# CH32F203VCT6-R0.net
KiCad netlist of a schematic drawn in Altium Designer
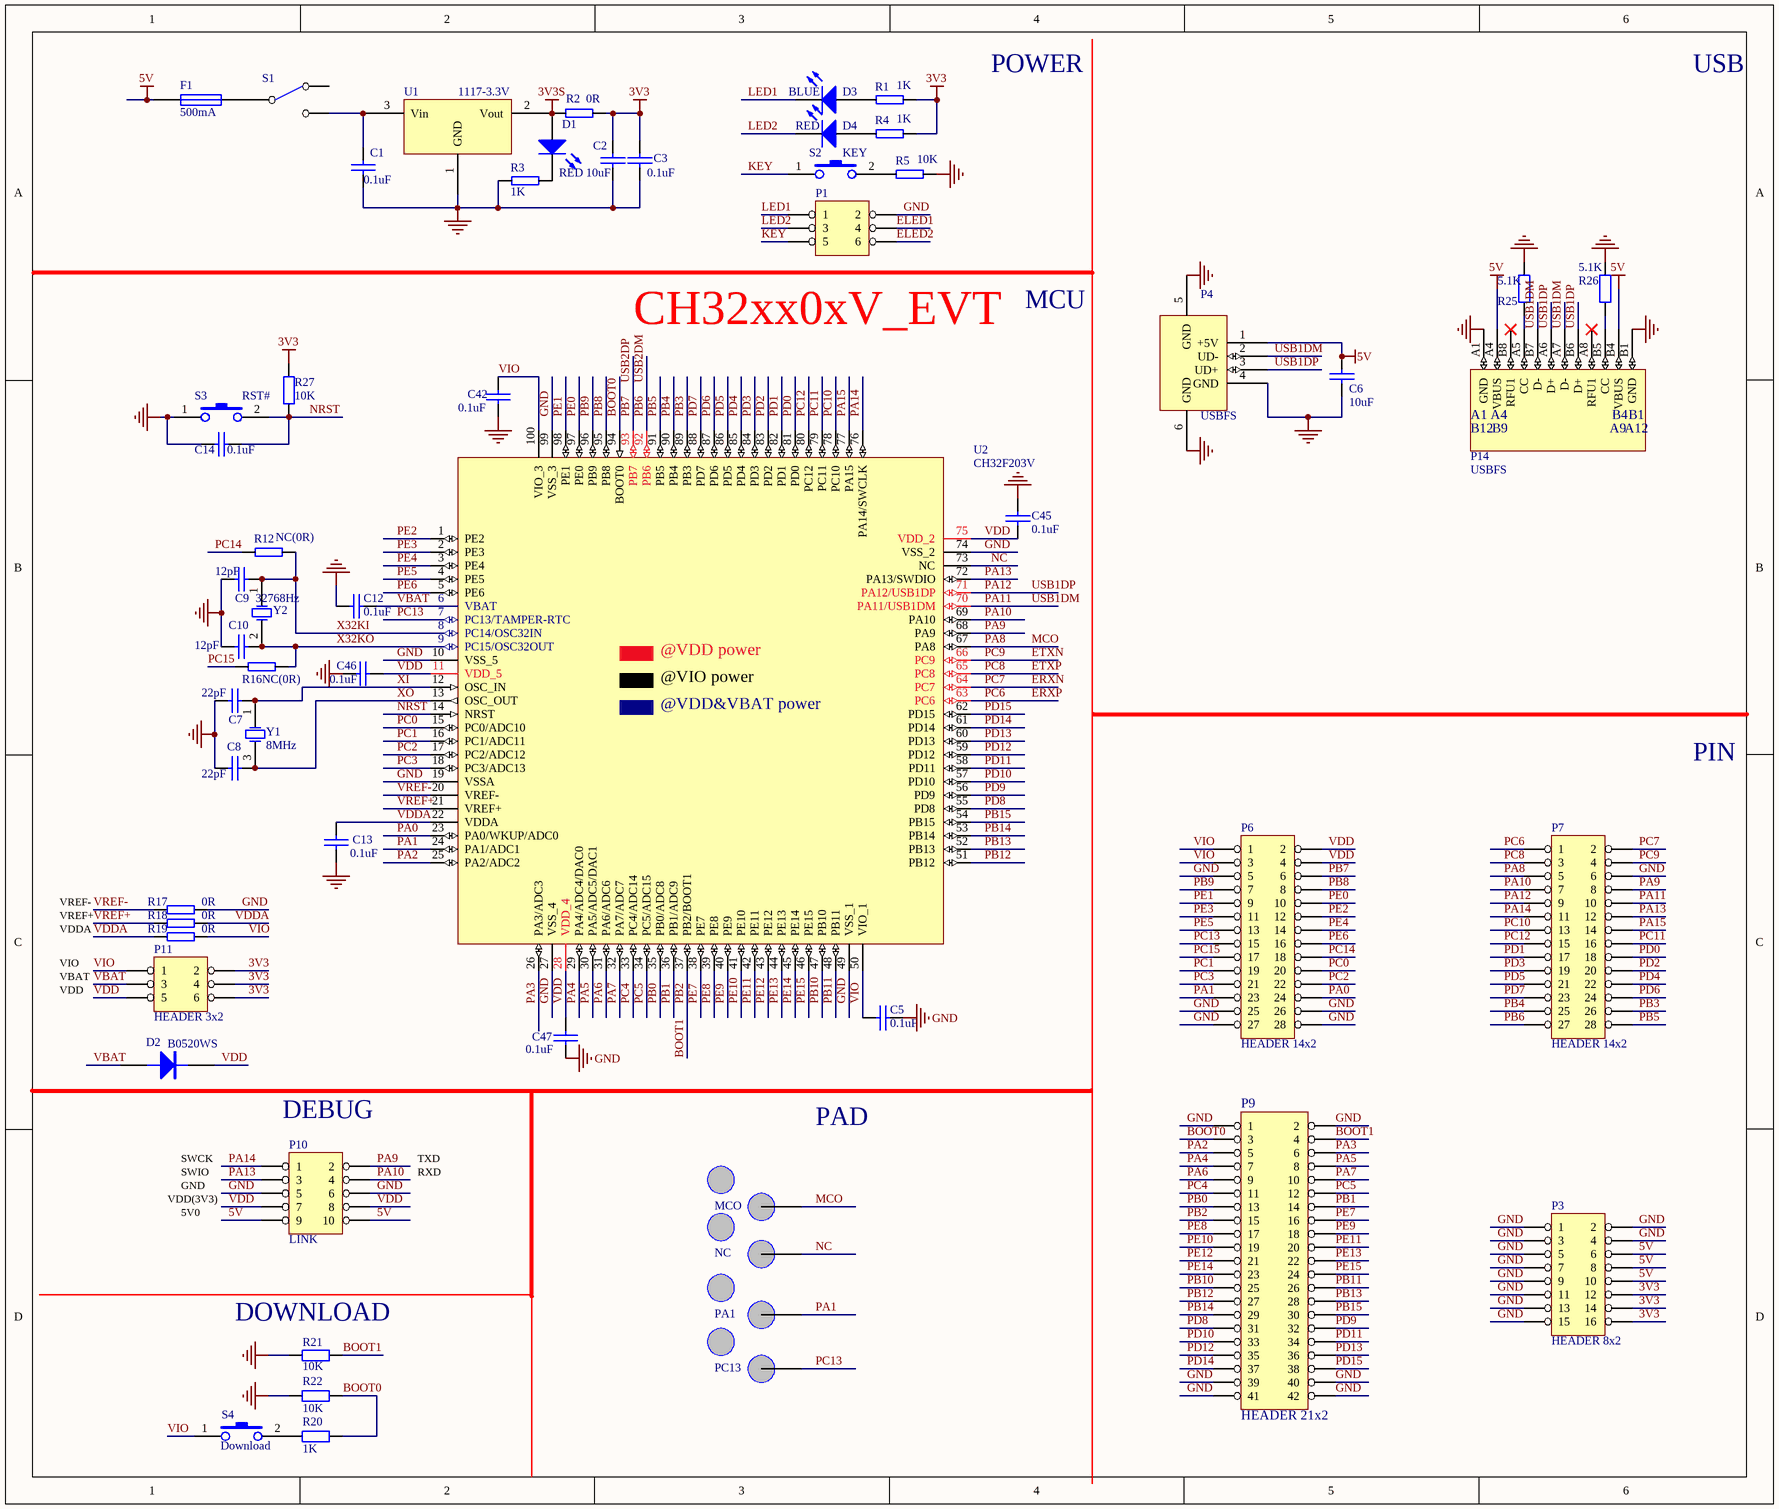
[diagram p0: CH32F203VCT6-R0.SchDoc]

(export (version "E")
  (design (tool "Eeschema 10.0.6"))
  (components
    (comp (ref "C1")
      (value "0.1uF")
      (footprint "0603_C")
      (description "Capacitor")
      (libsource (lib "*") (part "CAP"))
    )
    (comp (ref "C2")
      (value "10uF")
      (footprint "3216_C")
      (description "Capacitor")
      (libsource (lib "*") (part "CAP"))
    )
    (comp (ref "C3")
      (value "0.1uF")
      (footprint "0603_C")
      (description "Capacitor")
      (libsource (lib "*") (part "CAP"))
    )
    (comp (ref "C5")
      (value "0.1uF")
      (footprint "0603_C")
      (description "Capacitor")
      (libsource (lib "*") (part "CAP"))
    )
    (comp (ref "C6")
      (value "10uF")
      (footprint "3216_C")
      (description "Capacitor")
      (libsource (lib "") (part "CAP_1"))
    )
    (comp (ref "C7")
      (value "22pF")
      (footprint "0603_C")
      (description "Capacitor")
      (libsource (lib "*") (part "CAP"))
    )
    (comp (ref "C8")
      (value "22pF")
      (footprint "0603_C")
      (description "Capacitor")
      (libsource (lib "*") (part "CAP"))
    )
    (comp (ref "C9")
      (value "12pF")
      (footprint "0603_C")
      (description "Capacitor")
      (libsource (lib "*") (part "CAP"))
    )
    (comp (ref "C10")
      (value "12pF")
      (footprint "0603_C")
      (description "Capacitor")
      (libsource (lib "*") (part "CAP"))
    )
    (comp (ref "C12")
      (value "0.1uF")
      (footprint "0603_C")
      (description "Capacitor")
      (libsource (lib "*") (part "CAP"))
    )
    (comp (ref "C13")
      (value "0.1uF")
      (footprint "0603_C")
      (description "Capacitor")
      (libsource (lib "*") (part "CAP"))
    )
    (comp (ref "C14")
      (value "0.1uF")
      (footprint "0603_C")
      (description "Capacitor")
      (libsource (lib "") (part "CAP_1"))
    )
    (comp (ref "C42")
      (value "0.1uF")
      (footprint "0603_C")
      (description "Capacitor")
      (libsource (lib "*") (part "CAP"))
    )
    (comp (ref "C45")
      (value "0.1uF")
      (footprint "0603_C")
      (description "Capacitor")
      (libsource (lib "*") (part "CAP"))
    )
    (comp (ref "C46")
      (value "0.1uF")
      (footprint "0603_C")
      (description "Capacitor")
      (libsource (lib "*") (part "CAP"))
    )
    (comp (ref "C47")
      (value "0.1uF")
      (footprint "0603_C")
      (description "Capacitor")
      (libsource (lib "*") (part "CAP"))
    )
    (comp (ref "D1")
      (value "RED")
      (footprint "0603+")
      (description "Typical INFRARED GaAs LED")
      (fields (field (name "PUBLISHER") "Altium Limited"))
      (libsource (lib "*") (part "LED0"))
    )
    (comp (ref "D2")
      (value "B0520WS")
      (footprint "SOD-323")
      (description "Diode")
      (libsource (lib "*") (part "DIODE"))
    )
    (comp (ref "D3")
      (value "BLUE")
      (footprint "0603+")
      (description "Typical INFRARED GaAs LED")
      (fields (field (name "PUBLISHER") "Altium Limited"))
      (libsource (lib "*") (part "LED0"))
    )
    (comp (ref "D4")
      (value "RED")
      (footprint "0603+")
      (description "Typical INFRARED GaAs LED")
      (fields (field (name "PUBLISHER") "Altium Limited"))
      (libsource (lib "*") (part "LED0"))
    )
    (comp (ref "F1")
      (value "500mA")
      (footprint "0805")
      (description "Fuse")
      (libsource (lib "wch_sch_others") (part "FUSE1"))
    )
    (comp (ref "MCO")
      (value "Testpoint")
      (footprint "TESTPOINT1")
      (description "测试点")
      (libsource (lib "wch_sch_others") (part "Testpoint"))
    )
    (comp (ref "NC")
      (value "Testpoint")
      (footprint "TESTPOINT1")
      (description "测试点")
      (libsource (lib "wch_sch_others") (part "Testpoint"))
    )
    (comp (ref "P1")
      (value "IO")
      (footprint "MYPCB:IDC6-2.54mm")
      (description "Header, 3-Pin, Dual row")
      (libsource (lib "wch_sch_others") (part "HEADER 3x2"))
    )
    (comp (ref "P3")
      (value "HEADER 8x2")
      (footprint "MYPCB:IDC16-2.54mm")
      (description "Header, 8-Pin, Dual row")
      (libsource (lib "wch_sch_others") (part "HEADER 8x2"))
    )
    (comp (ref "P4")
      (value "USBFS")
      (footprint "USBAF")
      (description "USB Port")
      (libsource (lib "*") (part "USB"))
    )
    (comp (ref "P6")
      (value "HEADER 14x2")
      (footprint "MYPCB:IDC28-2.54MM")
      (description "Header, 14-Pin, Dual row")
      (libsource (lib "wch_sch_others") (part "HEADER 14x2"))
    )
    (comp (ref "P7")
      (value "HEADER 14x2")
      (footprint "MYPCB:IDC28-2.54MM")
      (description "Header, 14-Pin, Dual row")
      (libsource (lib "wch_sch_others") (part "HEADER 14x2"))
    )
    (comp (ref "P9")
      (value "HEADER 21x2")
      (footprint "MYPCB:IDC42-2.54MM")
      (description "Header, 21-Pin, Dual row")
      (libsource (lib "wch_sch_others") (part "HEADER 21x2"))
    )
    (comp (ref "P10")
      (value "LINK")
      (footprint "MYPCB:IDC10-2.54mm")
      (description "Header, 5-Pin, Dual row")
      (libsource (lib "wch_sch_others") (part "HEADER 5x2"))
    )
    (comp (ref "P11")
      (value "HEADER 3x2")
      (footprint "MYPCB:IDC6-2.54mm")
      (description "Header, 3-Pin, Dual row")
      (libsource (lib "wch_sch_others") (part "HEADER 3x2"))
    )
    (comp (ref "P14")
      (value "USBFS")
      (footprint "TYPE-C-Receptacle-2.0")
      (libsource (lib "*") (part "TYPE-C1"))
    )
    (comp (ref "PA1")
      (value "Testpoint")
      (footprint "TESTPOINT1")
      (description "测试点")
      (libsource (lib "wch_sch_others") (part "Testpoint"))
    )
    (comp (ref "PC13")
      (value "Testpoint")
      (footprint "TESTPOINT1")
      (description "测试点")
      (libsource (lib "wch_sch_others") (part "Testpoint"))
    )
    (comp (ref "R1") (value "1K") (footprint "0603") (libsource (lib "wch_sch_others") (part "RES")))
    (comp (ref "R2") (value "0R") (footprint "0603") (libsource (lib "wch_sch_others") (part "RES")))
    (comp (ref "R3") (value "1K") (footprint "0603") (libsource (lib "wch_sch_others") (part "RES")))
    (comp (ref "R4") (value "1K") (footprint "0603") (libsource (lib "wch_sch_others") (part "RES")))
    (comp (ref "R5") (value "10K") (footprint "0603") (libsource (lib "wch_sch_others") (part "RES")))
    (comp (ref "R12") (value "NC(0R)") (footprint "0603") (libsource (lib "wch_sch_others") (part "RES")))
    (comp (ref "R16") (value "NC(0R)") (footprint "0603") (libsource (lib "wch_sch_others") (part "RES")))
    (comp (ref "R17") (value "0R") (footprint "0603") (libsource (lib "*") (part "R")))
    (comp (ref "R18") (value "0R") (footprint "0603") (libsource (lib "*") (part "R")))
    (comp (ref "R19") (value "0R") (footprint "0603") (libsource (lib "*") (part "R")))
    (comp (ref "R20")
      (value "1K")
      (footprint "0603")
      (description "Resistor")
      (fields (field (name "PUBLISHER") "Altium Limited"))
      (libsource (lib "Miscellaneous Devices") (part "Res2"))
    )
    (comp (ref "R21")
      (value "10K")
      (footprint "0603")
      (description "Resistor")
      (fields (field (name "PUBLISHER") "Altium Limited"))
      (libsource (lib "Miscellaneous Devices") (part "Res2"))
    )
    (comp (ref "R22")
      (value "10K")
      (footprint "0603")
      (description "Resistor")
      (fields (field (name "PUBLISHER") "Altium Limited"))
      (libsource (lib "Miscellaneous Devices") (part "Res2"))
    )
    (comp (ref "R25")
      (value "5.1K")
      (footprint "0603")
      (description "Resistor")
      (libsource (lib "") (part "Res2_1"))
    )
    (comp (ref "R26")
      (value "5.1K")
      (footprint "0603")
      (description "Resistor")
      (libsource (lib "") (part "Res2_1"))
    )
    (comp (ref "R27")
      (value "10K")
      (footprint "0603")
      (description "Resistor")
      (fields (field (name "PUBLISHER") "Altium Limited"))
      (libsource (lib "") (part "Res2_1"))
    )
    (comp (ref "S1") (value "SW SPDT") (footprint "KEY2") (libsource (lib "*") (part "SW SPDT")))
    (comp (ref "S2")
      (value "KEY")
      (footprint "SMD_6.1x3.65x2.5mm-KEY")
      (libsource (lib "wch_sch_others") (part "KEY1"))
    )
    (comp (ref "S3")
      (value "RST#")
      (footprint "SMD_6.1x3.65x2.5mm-KEY")
      (libsource (lib "wch_sch_others") (part "KEY1"))
    )
    (comp (ref "S4")
      (value "Download")
      (footprint "SMD_6.1x3.65x2.5mm-KEY")
      (libsource (lib "wch_sch_others") (part "KEY1"))
    )
    (comp (ref "U1")
      (value "1117-3.3V")
      (footprint "SOT-223")
      (libsource (lib "wch_sch_others") (part "1117-3.3V"))
    )
    (comp (ref "U2")
      (value "CH32F203V")
      (footprint "LQFP100")
      (description "ARM M3 HD-MCU, 144MHz, 8*UART, 10*Timer, 4*OPA")
      (libsource (lib "CHXXX") (part "CH32F203V"))
    )
    (comp (ref "Y1")
      (value "8MHz")
      (footprint "XT3225")
      (description "Crystal Oscillator")
      (fields (field (name "PUBLISHER") "Altium Limited"))
      (libsource (lib "") (part "XTAL_1"))
    )
    (comp (ref "Y2")
      (value "32768Hz")
      (footprint "FC-135")
      (description "Crystal Oscillator")
      (fields (field (name "PUBLISHER") "Altium Limited"))
      (libsource (lib "*") (part "XTAL"))
    )
  )
  (nets
    (net (code "2") (name "/BOOT0") (class "Default")
      (node (ref "P9") (pin "3") (pinfunction "3_3") (pintype "passive"))
      (node (ref "R20") (pin "1") (pinfunction "1_1") (pintype "passive"))
      (node (ref "R22") (pin "1") (pinfunction "1_1") (pintype "passive"))
      (node (ref "U2") (pin "94") (pinfunction "BOOT0_94") (pintype "input"))
    )
    (net (code "3") (name "/BOOT1") (class "Default")
      (node (ref "P9") (pin "15") (pinfunction "15_15") (pintype "passive"))
      (node (ref "P9") (pin "4") (pinfunction "4_4") (pintype "passive"))
      (node (ref "R21") (pin "1") (pinfunction "1_1") (pintype "passive"))
      (node (ref "U2") (pin "37") (pinfunction "PB2/BOOT1_37") (pintype "bidirectional"))
    )
    (net (code "4") (name "/ELED1") (class "Default")
      (node (ref "P1") (pin "4") (pinfunction "4_4") (pintype "passive"))
    )
    (net (code "5") (name "/ELED2") (class "Default")
      (node (ref "P1") (pin "6") (pinfunction "6_6") (pintype "passive"))
    )
    (net (code "6") (name "/ERXN") (class "Default")
      (node (ref "P7") (pin "2") (pinfunction "2_2") (pintype "passive"))
      (node (ref "U2") (pin "64") (pinfunction "PC7_64") (pintype "bidirectional"))
    )
    (net (code "7") (name "/ERXP") (class "Default")
      (node (ref "P7") (pin "1") (pinfunction "1_1") (pintype "passive"))
      (node (ref "U2") (pin "63") (pinfunction "PC6_63") (pintype "bidirectional"))
    )
    (net (code "8") (name "/ETXN") (class "Default")
      (node (ref "P7") (pin "4") (pinfunction "4_4") (pintype "passive"))
      (node (ref "U2") (pin "66") (pinfunction "PC9_66") (pintype "bidirectional"))
    )
    (net (code "9") (name "/ETXP") (class "Default")
      (node (ref "P7") (pin "3") (pinfunction "3_3") (pintype "passive"))
      (node (ref "U2") (pin "65") (pinfunction "PC8_65") (pintype "bidirectional"))
    )
    (net (code "10") (name "/KEY") (class "Default")
      (node (ref "P1") (pin "5") (pinfunction "5_5") (pintype "passive"))
      (node (ref "S2") (pin "1") (pinfunction "1_1") (pintype "passive"))
    )
    (net (code "11") (name "/LED1") (class "Default")
      (node (ref "D3") (pin "2") (pinfunction "K_2") (pintype "passive"))
      (node (ref "P1") (pin "1") (pinfunction "1_1") (pintype "passive"))
    )
    (net (code "12") (name "/LED2") (class "Default")
      (node (ref "D4") (pin "2") (pinfunction "K_2") (pintype "passive"))
      (node (ref "P1") (pin "3") (pinfunction "3_3") (pintype "passive"))
    )
    (net (code "13") (name "/MCO") (class "Default")
      (node (ref "MCO") (pin "1") (pinfunction "point_1") (pintype "passive"))
      (node (ref "P7") (pin "5") (pinfunction "5_5") (pintype "passive"))
      (node (ref "U2") (pin "67") (pinfunction "PA8_67") (pintype "bidirectional"))
    )
    (net (code "14") (name "/NC") (class "Default")
      (node (ref "NC") (pin "1") (pinfunction "point_1") (pintype "passive"))
      (node (ref "U2") (pin "73") (pinfunction "NC_73") (pintype "tri_state"))
    )
    (net (code "15") (name "/NRST") (class "Default")
      (node (ref "C14") (pin "2") (pinfunction "2_2") (pintype "passive"))
      (node (ref "R27") (pin "1") (pinfunction "1_1") (pintype "passive"))
      (node (ref "S3") (pin "2") (pinfunction "2_2") (pintype "passive"))
      (node (ref "U2") (pin "14") (pinfunction "NRST_14") (pintype "input"))
    )
    (net (code "16") (name "/PA0") (class "Default")
      (node (ref "P6") (pin "24") (pinfunction "24_24") (pintype "passive"))
      (node (ref "U2") (pin "23") (pinfunction "PA0/WKUP/ADC0_23") (pintype "bidirectional"))
    )
    (net (code "17") (name "/PA1") (class "Default")
      (node (ref "P6") (pin "23") (pinfunction "23_23") (pintype "passive"))
      (node (ref "PA1") (pin "1") (pinfunction "point_1") (pintype "passive"))
      (node (ref "U2") (pin "24") (pinfunction "PA1/ADC1_24") (pintype "bidirectional"))
    )
    (net (code "18") (name "/PA2") (class "Default")
      (node (ref "P9") (pin "5") (pinfunction "5_5") (pintype "passive"))
      (node (ref "U2") (pin "25") (pinfunction "PA2/ADC2_25") (pintype "bidirectional"))
    )
    (net (code "19") (name "/PA3") (class "Default")
      (node (ref "P9") (pin "6") (pinfunction "6_6") (pintype "passive"))
      (node (ref "U2") (pin "26") (pinfunction "PA3/ADC3_26") (pintype "bidirectional"))
    )
    (net (code "20") (name "/PA4") (class "Default")
      (node (ref "P9") (pin "7") (pinfunction "7_7") (pintype "passive"))
      (node (ref "U2") (pin "29") (pinfunction "PA4/ADC4/DAC0_29") (pintype "bidirectional"))
    )
    (net (code "21") (name "/PA5") (class "Default")
      (node (ref "P9") (pin "8") (pinfunction "8_8") (pintype "passive"))
      (node (ref "U2") (pin "30") (pinfunction "PA5/ADC5/DAC1_30") (pintype "bidirectional"))
    )
    (net (code "22") (name "/PA6") (class "Default")
      (node (ref "P9") (pin "9") (pinfunction "9_9") (pintype "passive"))
      (node (ref "U2") (pin "31") (pinfunction "PA6/ADC6_31") (pintype "bidirectional"))
    )
    (net (code "23") (name "/PA7") (class "Default")
      (node (ref "P9") (pin "10") (pinfunction "10_10") (pintype "passive"))
      (node (ref "U2") (pin "32") (pinfunction "PA7/ADC7_32") (pintype "bidirectional"))
    )
    (net (code "24") (name "/PA9") (class "Default")
      (node (ref "P10") (pin "2") (pinfunction "2_2") (pintype "passive"))
      (node (ref "P7") (pin "8") (pinfunction "8_8") (pintype "passive"))
      (node (ref "U2") (pin "68") (pinfunction "PA9_68") (pintype "bidirectional"))
    )
    (net (code "25") (name "/PA10") (class "Default")
      (node (ref "P10") (pin "4") (pinfunction "4_4") (pintype "passive"))
      (node (ref "P7") (pin "7") (pinfunction "7_7") (pintype "passive"))
      (node (ref "U2") (pin "69") (pinfunction "PA10_69") (pintype "bidirectional"))
    )
    (net (code "26") (name "/PA11") (class "Default")
      (node (ref "P14") (pin "A7") (pinfunction "D-_A7") (pintype "bidirectional"))
      (node (ref "P14") (pin "B7") (pinfunction "D-_B7") (pintype "bidirectional"))
      (node (ref "P4") (pin "2") (pinfunction "UD-_2") (pintype "bidirectional"))
      (node (ref "P7") (pin "10") (pinfunction "10_10") (pintype "passive"))
      (node (ref "U2") (pin "70") (pinfunction "PA11/USB1DM_70") (pintype "bidirectional"))
    )
    (net (code "27") (name "/PA12") (class "Default")
      (node (ref "P14") (pin "A6") (pinfunction "D+_A6") (pintype "bidirectional"))
      (node (ref "P14") (pin "B6") (pinfunction "D+_B6") (pintype "bidirectional"))
      (node (ref "P4") (pin "3") (pinfunction "UD+_3") (pintype "bidirectional"))
      (node (ref "P7") (pin "9") (pinfunction "9_9") (pintype "passive"))
      (node (ref "U2") (pin "71") (pinfunction "PA12/USB1DP_71") (pintype "bidirectional"))
    )
    (net (code "28") (name "/PA13") (class "Default")
      (node (ref "P10") (pin "3") (pinfunction "3_3") (pintype "passive"))
      (node (ref "P7") (pin "12") (pinfunction "12_12") (pintype "passive"))
      (node (ref "U2") (pin "72") (pinfunction "PA13/SWDIO_72") (pintype "bidirectional"))
    )
    (net (code "29") (name "/PA14") (class "Default")
      (node (ref "P10") (pin "1") (pinfunction "1_1") (pintype "passive"))
      (node (ref "P7") (pin "11") (pinfunction "11_11") (pintype "passive"))
      (node (ref "U2") (pin "76") (pinfunction "PA14/SWCLK_76") (pintype "bidirectional"))
    )
    (net (code "30") (name "/PA15") (class "Default")
      (node (ref "P7") (pin "14") (pinfunction "14_14") (pintype "passive"))
      (node (ref "U2") (pin "77") (pinfunction "PA15_77") (pintype "bidirectional"))
    )
    (net (code "31") (name "/PB0") (class "Default")
      (node (ref "P9") (pin "13") (pinfunction "13_13") (pintype "passive"))
      (node (ref "U2") (pin "35") (pinfunction "PB0/ADC8_35") (pintype "bidirectional"))
    )
    (net (code "32") (name "/PB1") (class "Default")
      (node (ref "P9") (pin "14") (pinfunction "14_14") (pintype "passive"))
      (node (ref "U2") (pin "36") (pinfunction "PB1/ADC9_36") (pintype "bidirectional"))
    )
    (net (code "33") (name "/PB3") (class "Default")
      (node (ref "P7") (pin "26") (pinfunction "26_26") (pintype "passive"))
      (node (ref "U2") (pin "89") (pinfunction "PB3_89") (pintype "bidirectional"))
    )
    (net (code "34") (name "/PB4") (class "Default")
      (node (ref "P7") (pin "25") (pinfunction "25_25") (pintype "passive"))
      (node (ref "U2") (pin "90") (pinfunction "PB4_90") (pintype "bidirectional"))
    )
    (net (code "35") (name "/PB5") (class "Default")
      (node (ref "P7") (pin "28") (pinfunction "28_28") (pintype "passive"))
      (node (ref "U2") (pin "91") (pinfunction "PB5_91") (pintype "bidirectional"))
    )
    (net (code "36") (name "/PB6") (class "Default")
      (node (ref "P7") (pin "27") (pinfunction "27_27") (pintype "passive"))
      (node (ref "U2") (pin "92") (pinfunction "PB6_92") (pintype "bidirectional"))
    )
    (net (code "37") (name "/PB7") (class "Default")
      (node (ref "P6") (pin "6") (pinfunction "6_6") (pintype "passive"))
      (node (ref "U2") (pin "93") (pinfunction "PB7_93") (pintype "bidirectional"))
    )
    (net (code "38") (name "/PB8") (class "Default")
      (node (ref "P6") (pin "8") (pinfunction "8_8") (pintype "passive"))
      (node (ref "U2") (pin "95") (pinfunction "PB8_95") (pintype "bidirectional"))
    )
    (net (code "39") (name "/PB9") (class "Default")
      (node (ref "P6") (pin "7") (pinfunction "7_7") (pintype "passive"))
      (node (ref "U2") (pin "96") (pinfunction "PB9_96") (pintype "bidirectional"))
    )
    (net (code "40") (name "/PB10") (class "Default")
      (node (ref "P9") (pin "25") (pinfunction "25_25") (pintype "passive"))
      (node (ref "U2") (pin "47") (pinfunction "PB10_47") (pintype "bidirectional"))
    )
    (net (code "41") (name "/PB11") (class "Default")
      (node (ref "P9") (pin "26") (pinfunction "26_26") (pintype "passive"))
      (node (ref "U2") (pin "48") (pinfunction "PB11_48") (pintype "bidirectional"))
    )
    (net (code "42") (name "/PB12") (class "Default")
      (node (ref "P9") (pin "27") (pinfunction "27_27") (pintype "passive"))
      (node (ref "U2") (pin "51") (pinfunction "PB12_51") (pintype "bidirectional"))
    )
    (net (code "43") (name "/PB13") (class "Default")
      (node (ref "P9") (pin "28") (pinfunction "28_28") (pintype "passive"))
      (node (ref "U2") (pin "52") (pinfunction "PB13_52") (pintype "bidirectional"))
    )
    (net (code "44") (name "/PB14") (class "Default")
      (node (ref "P9") (pin "29") (pinfunction "29_29") (pintype "passive"))
      (node (ref "U2") (pin "53") (pinfunction "PB14_53") (pintype "bidirectional"))
    )
    (net (code "45") (name "/PB15") (class "Default")
      (node (ref "P9") (pin "30") (pinfunction "30_30") (pintype "passive"))
      (node (ref "U2") (pin "54") (pinfunction "PB15_54") (pintype "bidirectional"))
    )
    (net (code "46") (name "/PC0") (class "Default")
      (node (ref "P6") (pin "20") (pinfunction "20_20") (pintype "passive"))
      (node (ref "U2") (pin "15") (pinfunction "PC0/ADC10_15") (pintype "bidirectional"))
    )
    (net (code "47") (name "/PC1") (class "Default")
      (node (ref "P6") (pin "19") (pinfunction "19_19") (pintype "passive"))
      (node (ref "U2") (pin "16") (pinfunction "PC1/ADC11_16") (pintype "bidirectional"))
    )
    (net (code "48") (name "/PC2") (class "Default")
      (node (ref "P6") (pin "22") (pinfunction "22_22") (pintype "passive"))
      (node (ref "U2") (pin "17") (pinfunction "PC2/ADC12_17") (pintype "bidirectional"))
    )
    (net (code "49") (name "/PC3") (class "Default")
      (node (ref "P6") (pin "21") (pinfunction "21_21") (pintype "passive"))
      (node (ref "U2") (pin "18") (pinfunction "PC3/ADC13_18") (pintype "bidirectional"))
    )
    (net (code "50") (name "/PC4") (class "Default")
      (node (ref "P9") (pin "11") (pinfunction "11_11") (pintype "passive"))
      (node (ref "U2") (pin "33") (pinfunction "PC4/ADC14_33") (pintype "bidirectional"))
    )
    (net (code "51") (name "/PC5") (class "Default")
      (node (ref "P9") (pin "12") (pinfunction "12_12") (pintype "passive"))
      (node (ref "U2") (pin "34") (pinfunction "PC5/ADC15_34") (pintype "bidirectional"))
    )
    (net (code "52") (name "/PC10") (class "Default")
      (node (ref "P7") (pin "13") (pinfunction "13_13") (pintype "passive"))
      (node (ref "U2") (pin "78") (pinfunction "PC10_78") (pintype "bidirectional"))
    )
    (net (code "53") (name "/PC11") (class "Default")
      (node (ref "P7") (pin "16") (pinfunction "16_16") (pintype "passive"))
      (node (ref "U2") (pin "79") (pinfunction "PC11_79") (pintype "bidirectional"))
    )
    (net (code "54") (name "/PC12") (class "Default")
      (node (ref "P7") (pin "15") (pinfunction "15_15") (pintype "passive"))
      (node (ref "U2") (pin "80") (pinfunction "PC12_80") (pintype "bidirectional"))
    )
    (net (code "55") (name "/PC13") (class "Default")
      (node (ref "P6") (pin "15") (pinfunction "15_15") (pintype "passive"))
      (node (ref "PC13") (pin "1") (pinfunction "point_1") (pintype "passive"))
      (node (ref "U2") (pin "7") (pinfunction "PC13/TAMPER-RTC_7") (pintype "bidirectional"))
    )
    (net (code "56") (name "/PC14") (class "Default")
      (node (ref "P6") (pin "18") (pinfunction "18_18") (pintype "passive"))
      (node (ref "R12") (pin "1") (pintype "passive"))
    )
    (net (code "57") (name "/PC15") (class "Default")
      (node (ref "P6") (pin "17") (pinfunction "17_17") (pintype "passive"))
      (node (ref "R16") (pin "1") (pintype "passive"))
    )
    (net (code "58") (name "/PD0") (class "Default")
      (node (ref "P7") (pin "18") (pinfunction "18_18") (pintype "passive"))
      (node (ref "U2") (pin "81") (pinfunction "PD0_81") (pintype "bidirectional"))
    )
    (net (code "59") (name "/PD1") (class "Default")
      (node (ref "P7") (pin "17") (pinfunction "17_17") (pintype "passive"))
      (node (ref "U2") (pin "82") (pinfunction "PD1_82") (pintype "bidirectional"))
    )
    (net (code "60") (name "/PD2") (class "Default")
      (node (ref "P7") (pin "20") (pinfunction "20_20") (pintype "passive"))
      (node (ref "U2") (pin "83") (pinfunction "PD2_83") (pintype "bidirectional"))
    )
    (net (code "61") (name "/PD3") (class "Default")
      (node (ref "P7") (pin "19") (pinfunction "19_19") (pintype "passive"))
      (node (ref "U2") (pin "84") (pinfunction "PD3_84") (pintype "bidirectional"))
    )
    (net (code "62") (name "/PD4") (class "Default")
      (node (ref "P7") (pin "22") (pinfunction "22_22") (pintype "passive"))
      (node (ref "U2") (pin "85") (pinfunction "PD4_85") (pintype "bidirectional"))
    )
    (net (code "63") (name "/PD5") (class "Default")
      (node (ref "P7") (pin "21") (pinfunction "21_21") (pintype "passive"))
      (node (ref "U2") (pin "86") (pinfunction "PD5_86") (pintype "bidirectional"))
    )
    (net (code "64") (name "/PD6") (class "Default")
      (node (ref "P7") (pin "24") (pinfunction "24_24") (pintype "passive"))
      (node (ref "U2") (pin "87") (pinfunction "PD6_87") (pintype "bidirectional"))
    )
    (net (code "65") (name "/PD7") (class "Default")
      (node (ref "P7") (pin "23") (pinfunction "23_23") (pintype "passive"))
      (node (ref "U2") (pin "88") (pinfunction "PD7_88") (pintype "bidirectional"))
    )
    (net (code "66") (name "/PD8") (class "Default")
      (node (ref "P9") (pin "31") (pinfunction "31_31") (pintype "passive"))
      (node (ref "U2") (pin "55") (pinfunction "PD8_55") (pintype "bidirectional"))
    )
    (net (code "67") (name "/PD9") (class "Default")
      (node (ref "P9") (pin "32") (pinfunction "32_32") (pintype "passive"))
      (node (ref "U2") (pin "56") (pinfunction "PD9_56") (pintype "bidirectional"))
    )
    (net (code "68") (name "/PD10") (class "Default")
      (node (ref "P9") (pin "33") (pinfunction "33_33") (pintype "passive"))
      (node (ref "U2") (pin "57") (pinfunction "PD10_57") (pintype "bidirectional"))
    )
    (net (code "69") (name "/PD11") (class "Default")
      (node (ref "P9") (pin "34") (pinfunction "34_34") (pintype "passive"))
      (node (ref "U2") (pin "58") (pinfunction "PD11_58") (pintype "bidirectional"))
    )
    (net (code "70") (name "/PD12") (class "Default")
      (node (ref "P9") (pin "35") (pinfunction "35_35") (pintype "passive"))
      (node (ref "U2") (pin "59") (pinfunction "PD12_59") (pintype "bidirectional"))
    )
    (net (code "71") (name "/PD13") (class "Default")
      (node (ref "P9") (pin "36") (pinfunction "36_36") (pintype "passive"))
      (node (ref "U2") (pin "60") (pinfunction "PD13_60") (pintype "bidirectional"))
    )
    (net (code "72") (name "/PD14") (class "Default")
      (node (ref "P9") (pin "37") (pinfunction "37_37") (pintype "passive"))
      (node (ref "U2") (pin "61") (pinfunction "PD14_61") (pintype "bidirectional"))
    )
    (net (code "73") (name "/PD15") (class "Default")
      (node (ref "P9") (pin "38") (pinfunction "38_38") (pintype "passive"))
      (node (ref "U2") (pin "62") (pinfunction "PD15_62") (pintype "bidirectional"))
    )
    (net (code "74") (name "/PE0") (class "Default")
      (node (ref "P6") (pin "10") (pinfunction "10_10") (pintype "passive"))
      (node (ref "U2") (pin "97") (pinfunction "PE0_97") (pintype "bidirectional"))
    )
    (net (code "75") (name "/PE1") (class "Default")
      (node (ref "P6") (pin "9") (pinfunction "9_9") (pintype "passive"))
      (node (ref "U2") (pin "98") (pinfunction "PE1_98") (pintype "bidirectional"))
    )
    (net (code "76") (name "/PE2") (class "Default")
      (node (ref "P6") (pin "12") (pinfunction "12_12") (pintype "passive"))
      (node (ref "U2") (pin "1") (pinfunction "PE2_1") (pintype "bidirectional"))
    )
    (net (code "77") (name "/PE3") (class "Default")
      (node (ref "P6") (pin "11") (pinfunction "11_11") (pintype "passive"))
      (node (ref "U2") (pin "2") (pinfunction "PE3_2") (pintype "bidirectional"))
    )
    (net (code "78") (name "/PE4") (class "Default")
      (node (ref "P6") (pin "14") (pinfunction "14_14") (pintype "passive"))
      (node (ref "U2") (pin "3") (pinfunction "PE4_3") (pintype "bidirectional"))
    )
    (net (code "79") (name "/PE5") (class "Default")
      (node (ref "P6") (pin "13") (pinfunction "13_13") (pintype "passive"))
      (node (ref "U2") (pin "4") (pinfunction "PE5_4") (pintype "bidirectional"))
    )
    (net (code "80") (name "/PE6") (class "Default")
      (node (ref "P6") (pin "16") (pinfunction "16_16") (pintype "passive"))
      (node (ref "U2") (pin "5") (pinfunction "PE6_5") (pintype "bidirectional"))
    )
    (net (code "81") (name "/PE7") (class "Default")
      (node (ref "P9") (pin "16") (pinfunction "16_16") (pintype "passive"))
      (node (ref "U2") (pin "38") (pinfunction "PE7_38") (pintype "bidirectional"))
    )
    (net (code "82") (name "/PE8") (class "Default")
      (node (ref "P9") (pin "17") (pinfunction "17_17") (pintype "passive"))
      (node (ref "U2") (pin "39") (pinfunction "PE8_39") (pintype "bidirectional"))
    )
    (net (code "83") (name "/PE9") (class "Default")
      (node (ref "P9") (pin "18") (pinfunction "18_18") (pintype "passive"))
      (node (ref "U2") (pin "40") (pinfunction "PE9_40") (pintype "bidirectional"))
    )
    (net (code "84") (name "/PE10") (class "Default")
      (node (ref "P9") (pin "19") (pinfunction "19_19") (pintype "passive"))
      (node (ref "U2") (pin "41") (pinfunction "PE10_41") (pintype "bidirectional"))
    )
    (net (code "85") (name "/PE11") (class "Default")
      (node (ref "P9") (pin "20") (pinfunction "20_20") (pintype "passive"))
      (node (ref "U2") (pin "42") (pinfunction "PE11_42") (pintype "bidirectional"))
    )
    (net (code "86") (name "/PE12") (class "Default")
      (node (ref "P9") (pin "21") (pinfunction "21_21") (pintype "passive"))
      (node (ref "U2") (pin "43") (pinfunction "PE12_43") (pintype "bidirectional"))
    )
    (net (code "87") (name "/PE13") (class "Default")
      (node (ref "P9") (pin "22") (pinfunction "22_22") (pintype "passive"))
      (node (ref "U2") (pin "44") (pinfunction "PE13_44") (pintype "bidirectional"))
    )
    (net (code "88") (name "/PE14") (class "Default")
      (node (ref "P9") (pin "23") (pinfunction "23_23") (pintype "passive"))
      (node (ref "U2") (pin "45") (pinfunction "PE14_45") (pintype "bidirectional"))
    )
    (net (code "89") (name "/PE15") (class "Default")
      (node (ref "P9") (pin "24") (pinfunction "24_24") (pintype "passive"))
      (node (ref "U2") (pin "46") (pinfunction "PE15_46") (pintype "bidirectional"))
    )
    (net (code "90") (name "/VBAT") (class "Default")
      (node (ref "C12") (pin "2") (pinfunction "2_2") (pintype "passive"))
      (node (ref "D2") (pin "1") (pinfunction "A_1") (pintype "passive"))
      (node (ref "P11") (pin "3") (pinfunction "3_3") (pintype "passive"))
      (node (ref "U2") (pin "6") (pinfunction "VBAT_6") (pintype "power_in"))
    )
    (net (code "91") (name "/VDD") (class "Default")
      (node (ref "C45") (pin "1") (pinfunction "1_1") (pintype "passive"))
      (node (ref "C46") (pin "1") (pinfunction "1_1") (pintype "passive"))
      (node (ref "C47") (pin "2") (pinfunction "2_2") (pintype "passive"))
      (node (ref "D2") (pin "2") (pinfunction "K_2") (pintype "passive"))
      (node (ref "P10") (pin "7") (pinfunction "7_7") (pintype "passive"))
      (node (ref "P10") (pin "8") (pinfunction "8_8") (pintype "passive"))
      (node (ref "P11") (pin "5") (pinfunction "5_5") (pintype "passive"))
      (node (ref "P6") (pin "2") (pinfunction "2_2") (pintype "passive"))
      (node (ref "P6") (pin "4") (pinfunction "4_4") (pintype "passive"))
      (node (ref "U2") (pin "11") (pinfunction "VDD_5_11") (pintype "power_in"))
      (node (ref "U2") (pin "28") (pinfunction "VDD_4_28") (pintype "power_in"))
      (node (ref "U2") (pin "75") (pinfunction "VDD_2_75") (pintype "power_in"))
    )
    (net (code "92") (name "/VDDA") (class "Default")
      (node (ref "C13") (pin "1") (pinfunction "1_1") (pintype "passive"))
      (node (ref "R18") (pin "1") (pinfunction "1_1") (pintype "passive"))
      (node (ref "R19") (pin "2") (pinfunction "2_2") (pintype "passive"))
      (node (ref "U2") (pin "22") (pinfunction "VDDA_22") (pintype "power_in"))
    )
    (net (code "93") (name "/VIO") (class "Default")
      (node (ref "C42") (pin "2") (pinfunction "2_2") (pintype "passive"))
      (node (ref "C5") (pin "1") (pinfunction "1_1") (pintype "passive"))
      (node (ref "P11") (pin "1") (pinfunction "1_1") (pintype "passive"))
      (node (ref "P6") (pin "1") (pinfunction "1_1") (pintype "passive"))
      (node (ref "P6") (pin "3") (pinfunction "3_3") (pintype "passive"))
      (node (ref "R19") (pin "1") (pinfunction "1_1") (pintype "passive"))
      (node (ref "S4") (pin "1") (pinfunction "1_1") (pintype "passive"))
      (node (ref "U2") (pin "100") (pinfunction "VIO_3_100") (pintype "power_in"))
      (node (ref "U2") (pin "50") (pinfunction "VIO_1_50") (pintype "power_in"))
    )
    (net (code "94") (name "/VREF+") (class "Default")
      (node (ref "R18") (pin "2") (pinfunction "2_2") (pintype "passive"))
      (node (ref "U2") (pin "21") (pinfunction "VREF+_21") (pintype "power_in"))
    )
    (net (code "95") (name "/VREF-") (class "Default")
      (node (ref "R17") (pin "2") (pinfunction "2_2") (pintype "passive"))
      (node (ref "U2") (pin "20") (pinfunction "VREF-_20") (pintype "power_in"))
    )
    (net (code "96") (name "/X32KI") (class "Default")
      (node (ref "C9") (pin "2") (pinfunction "2_2") (pintype "passive"))
      (node (ref "R12") (pin "2") (pintype "passive"))
      (node (ref "U2") (pin "8") (pinfunction "PC14/OSC32IN_8") (pintype "bidirectional"))
      (node (ref "Y2") (pin "1") (pinfunction "OSC1_1") (pintype "passive"))
    )
    (net (code "97") (name "/X32KO") (class "Default")
      (node (ref "C10") (pin "2") (pinfunction "2_2") (pintype "passive"))
      (node (ref "R16") (pin "2") (pintype "passive"))
      (node (ref "U2") (pin "9") (pinfunction "PC15/OSC32OUT_9") (pintype "bidirectional"))
      (node (ref "Y2") (pin "2") (pinfunction "OSC2_2") (pintype "passive"))
    )
    (net (code "98") (name "/XI") (class "Default")
      (node (ref "C7") (pin "2") (pinfunction "2_2") (pintype "passive"))
      (node (ref "U2") (pin "12") (pinfunction "OSC_IN_12") (pintype "input"))
      (node (ref "Y1") (pin "1") (pinfunction "OSC1_1") (pintype "passive"))
    )
    (net (code "99") (name "/XO") (class "Default")
      (node (ref "C8") (pin "2") (pinfunction "2_2") (pintype "passive"))
      (node (ref "U2") (pin "13") (pinfunction "OSC_OUT_13") (pintype "output"))
      (node (ref "Y1") (pin "3") (pinfunction "OSC2_3") (pintype "passive"))
    )
    (net (code "100") (name "3V3") (class "Default")
      (node (ref "C2") (pin "1") (pinfunction "1_1") (pintype "passive"))
      (node (ref "C3") (pin "1") (pinfunction "1_1") (pintype "passive"))
      (node (ref "P11") (pin "2") (pinfunction "2_2") (pintype "passive"))
      (node (ref "P11") (pin "4") (pinfunction "4_4") (pintype "passive"))
      (node (ref "P11") (pin "6") (pinfunction "6_6") (pintype "passive"))
      (node (ref "P3") (pin "12") (pinfunction "12_12") (pintype "passive"))
      (node (ref "P3") (pin "14") (pinfunction "14_14") (pintype "passive"))
      (node (ref "P3") (pin "16") (pinfunction "16_16") (pintype "passive"))
      (node (ref "R1") (pin "1") (pintype "passive"))
      (node (ref "R2") (pin "1") (pintype "passive"))
      (node (ref "R27") (pin "2") (pinfunction "2_2") (pintype "passive"))
      (node (ref "R4") (pin "1") (pintype "passive"))
    )
    (net (code "101") (name "3V3S") (class "Default")
      (node (ref "D1") (pin "1") (pinfunction "A_1") (pintype "passive"))
      (node (ref "R2") (pin "2") (pintype "passive"))
      (node (ref "U1") (pin "2") (pinfunction "Vout_2") (pintype "passive"))
    )
    (net (code "102") (name "5V") (class "Default")
      (node (ref "C6") (pin "1") (pinfunction "1_1") (pintype "passive"))
      (node (ref "F1") (pin "1") (pinfunction "1_1") (pintype "passive"))
      (node (ref "P10") (pin "10") (pinfunction "10_10") (pintype "passive"))
      (node (ref "P10") (pin "9") (pinfunction "9_9") (pintype "passive"))
      (node (ref "P14") (pin "A4") (pinfunction "VBUS_A4") (pintype "bidirectional"))
      (node (ref "P14") (pin "B4") (pinfunction "VBUS_B4") (pintype "bidirectional"))
      (node (ref "P3") (pin "10") (pinfunction "10_10") (pintype "passive"))
      (node (ref "P3") (pin "6") (pinfunction "6_6") (pintype "passive"))
      (node (ref "P3") (pin "8") (pinfunction "8_8") (pintype "passive"))
      (node (ref "P4") (pin "1") (pinfunction "+5V_1") (pintype "power_in"))
    )
    (net (code "103") (name "GND") (class "Default")
      (node (ref "C1") (pin "2") (pinfunction "2_2") (pintype "passive"))
      (node (ref "C10") (pin "1") (pinfunction "1_1") (pintype "passive"))
      (node (ref "C12") (pin "1") (pinfunction "1_1") (pintype "passive"))
      (node (ref "C13") (pin "2") (pinfunction "2_2") (pintype "passive"))
      (node (ref "C14") (pin "1") (pinfunction "1_1") (pintype "passive"))
      (node (ref "C2") (pin "2") (pinfunction "2_2") (pintype "passive"))
      (node (ref "C3") (pin "2") (pinfunction "2_2") (pintype "passive"))
      (node (ref "C42") (pin "1") (pinfunction "1_1") (pintype "passive"))
      (node (ref "C45") (pin "2") (pinfunction "2_2") (pintype "passive"))
      (node (ref "C46") (pin "2") (pinfunction "2_2") (pintype "passive"))
      (node (ref "C47") (pin "1") (pinfunction "1_1") (pintype "passive"))
      (node (ref "C5") (pin "2") (pinfunction "2_2") (pintype "passive"))
      (node (ref "C6") (pin "2") (pinfunction "2_2") (pintype "passive"))
      (node (ref "C7") (pin "1") (pinfunction "1_1") (pintype "passive"))
      (node (ref "C8") (pin "1") (pinfunction "1_1") (pintype "passive"))
      (node (ref "C9") (pin "1") (pinfunction "1_1") (pintype "passive"))
      (node (ref "P1") (pin "2") (pinfunction "2_2") (pintype "passive"))
      (node (ref "P10") (pin "5") (pinfunction "5_5") (pintype "passive"))
      (node (ref "P10") (pin "6") (pinfunction "6_6") (pintype "passive"))
      (node (ref "P14") (pin "A1") (pinfunction "GND_A1") (pintype "bidirectional"))
      (node (ref "P14") (pin "B1") (pinfunction "GND_B1") (pintype "bidirectional"))
      (node (ref "P3") (pin "1") (pinfunction "1_1") (pintype "passive"))
      (node (ref "P3") (pin "11") (pinfunction "11_11") (pintype "passive"))
      (node (ref "P3") (pin "13") (pinfunction "13_13") (pintype "passive"))
      (node (ref "P3") (pin "15") (pinfunction "15_15") (pintype "passive"))
      (node (ref "P3") (pin "2") (pinfunction "2_2") (pintype "passive"))
      (node (ref "P3") (pin "3") (pinfunction "3_3") (pintype "passive"))
      (node (ref "P3") (pin "4") (pinfunction "4_4") (pintype "passive"))
      (node (ref "P3") (pin "5") (pinfunction "5_5") (pintype "passive"))
      (node (ref "P3") (pin "7") (pinfunction "7_7") (pintype "passive"))
      (node (ref "P3") (pin "9") (pinfunction "9_9") (pintype "passive"))
      (node (ref "P4") (pin "4") (pinfunction "GND_4") (pintype "power_in"))
      (node (ref "P4") (pin "5") (pinfunction "GND_5") (pintype "power_in"))
      (node (ref "P4") (pin "6") (pinfunction "GND_6") (pintype "power_in"))
      (node (ref "P6") (pin "25") (pinfunction "25_25") (pintype "passive"))
      (node (ref "P6") (pin "26") (pinfunction "26_26") (pintype "passive"))
      (node (ref "P6") (pin "27") (pinfunction "27_27") (pintype "passive"))
      (node (ref "P6") (pin "28") (pinfunction "28_28") (pintype "passive"))
      (node (ref "P6") (pin "5") (pinfunction "5_5") (pintype "passive"))
      (node (ref "P7") (pin "6") (pinfunction "6_6") (pintype "passive"))
      (node (ref "P9") (pin "1") (pinfunction "1_1") (pintype "passive"))
      (node (ref "P9") (pin "2") (pinfunction "2_2") (pintype "passive"))
      (node (ref "P9") (pin "39") (pinfunction "39_39") (pintype "passive"))
      (node (ref "P9") (pin "40") (pinfunction "40_40") (pintype "passive"))
      (node (ref "P9") (pin "41") (pinfunction "41_41") (pintype "passive"))
      (node (ref "P9") (pin "42") (pinfunction "42_42") (pintype "passive"))
      (node (ref "R17") (pin "1") (pinfunction "1_1") (pintype "passive"))
      (node (ref "R21") (pin "2") (pinfunction "2_2") (pintype "passive"))
      (node (ref "R22") (pin "2") (pinfunction "2_2") (pintype "passive"))
      (node (ref "R25") (pin "2") (pinfunction "2_2") (pintype "passive"))
      (node (ref "R26") (pin "2") (pinfunction "2_2") (pintype "passive"))
      (node (ref "R3") (pin "2") (pintype "passive"))
      (node (ref "R5") (pin "1") (pintype "passive"))
      (node (ref "S3") (pin "1") (pinfunction "1_1") (pintype "passive"))
      (node (ref "U1") (pin "1") (pinfunction "GND_1") (pintype "passive"))
      (node (ref "U2") (pin "10") (pinfunction "VSS_5_10") (pintype "power_in"))
      (node (ref "U2") (pin "19") (pinfunction "VSSA_19") (pintype "power_in"))
      (node (ref "U2") (pin "27") (pinfunction "VSS_4_27") (pintype "power_in"))
      (node (ref "U2") (pin "49") (pinfunction "VSS_1_49") (pintype "power_in"))
      (node (ref "U2") (pin "74") (pinfunction "VSS_2_74") (pintype "power_in"))
      (node (ref "U2") (pin "99") (pinfunction "VSS_3_99") (pintype "power_in"))
    )
    (net (code "104") (name "Net-(D1-K)") (class "Default")
      (node (ref "D1") (pin "2") (pinfunction "K_2") (pintype "passive"))
      (node (ref "R3") (pin "1") (pintype "passive"))
    )
    (net (code "105") (name "Net-(D3-A)") (class "Default")
      (node (ref "D3") (pin "1") (pinfunction "A_1") (pintype "passive"))
      (node (ref "R1") (pin "2") (pintype "passive"))
    )
    (net (code "106") (name "Net-(D4-A)") (class "Default")
      (node (ref "D4") (pin "1") (pinfunction "A_1") (pintype "passive"))
      (node (ref "R4") (pin "2") (pintype "passive"))
    )
    (net (code "107") (name "Net-(P14-CC-PadA5)") (class "Default")
      (node (ref "P14") (pin "A5") (pinfunction "CC_A5") (pintype "bidirectional"))
      (node (ref "R25") (pin "1") (pinfunction "1_1") (pintype "passive"))
    )
    (net (code "108") (name "Net-(P14-CC-PadB5)") (class "Default")
      (node (ref "P14") (pin "B5") (pinfunction "CC_B5") (pintype "bidirectional"))
      (node (ref "R26") (pin "1") (pinfunction "1_1") (pintype "passive"))
    )
    (net (code "109") (name "Net-(R5-Pad2)") (class "Default")
      (node (ref "R5") (pin "2") (pintype "passive"))
      (node (ref "S2") (pin "2") (pinfunction "2_2") (pintype "passive"))
    )
    (net (code "110") (name "Net-(R20-Pad2)") (class "Default")
      (node (ref "R20") (pin "2") (pinfunction "2_2") (pintype "passive"))
      (node (ref "S4") (pin "2") (pinfunction "2_2") (pintype "passive"))
    )
    (net (code "111") (name "Net-(S1-COMMON)") (class "Default")
      (node (ref "F1") (pin "2") (pinfunction "2_2") (pintype "passive"))
      (node (ref "S1") (pin "1") (pinfunction "COMMON_1") (pintype "passive"))
    )
    (net (code "112") (name "Net-(S1-NC)") (class "Default")
      (node (ref "C1") (pin "1") (pinfunction "1_1") (pintype "passive"))
      (node (ref "S1") (pin "2") (pinfunction "NC_2") (pintype "passive"))
      (node (ref "U1") (pin "3") (pinfunction "Vin_3") (pintype "passive"))
    )
    (net (code "113") (name "unconnected-(P14-RFU1-PadA8)") (class "Default")
      (node (ref "P14") (pin "A8") (pinfunction "RFU1_A8") (pintype "bidirectional+no_connect"))
    )
    (net (code "114") (name "unconnected-(P14-RFU1-PadB8)") (class "Default")
      (node (ref "P14") (pin "B8") (pinfunction "RFU1_B8") (pintype "bidirectional+no_connect"))
    )
    (net (code "115") (name "unconnected-(S1-NO-Pad3)") (class "Default")
      (node (ref "S1") (pin "3") (pinfunction "NO_3") (pintype "passive"))
    )
  )
)
